# LSM6DS3.net
KiCad netlist of a schematic drawn in Altium Designer
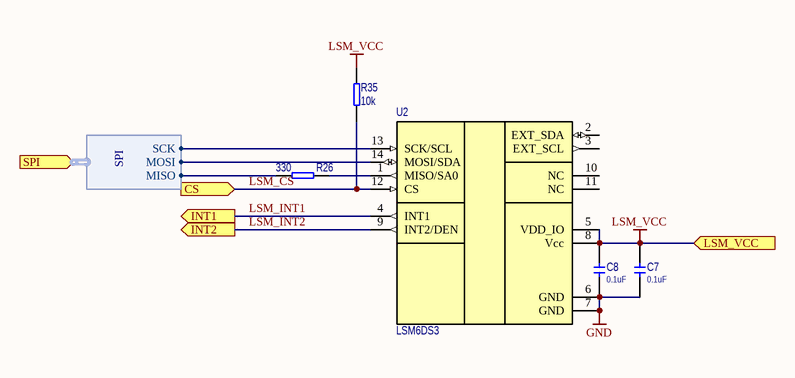
[diagram p0: LSM6DS3.SchDoc]

(export (version "E")
  (design (tool "Eeschema 10.0.6"))
  (components
    (comp (ref "C7")
      (value "0.1uF")
      (footprint "CERCAP 0603")
      (description "Capacitor")
      (fields (field (name "Comment") "CERCAP 0603 0.1uF * X7R"))
      (libsource (lib "!main") (part "!Capacitor"))
    )
    (comp (ref "C8")
      (value "0.1uF")
      (footprint "CERCAP 0603")
      (description "Capacitor")
      (fields (field (name "Comment") "CERCAP 0603 0.1uF * X7R"))
      (libsource (lib "!main") (part "!Capacitor"))
    )
    (comp (ref "R26")
      (value "330")
      (footprint "RES 0603")
      (description "Resistor")
      (fields (field (name "Comment") "RES 0603 330"))
      (libsource (lib "!main") (part "!Resistor"))
    )
    (comp (ref "R35")
      (value "10k")
      (footprint "RES 0603")
      (description "Resistor")
      (fields (field (name "Comment") "RES 0603 10k"))
      (libsource (lib "!main") (part "!Resistor"))
    )
    (comp (ref "U2")
      (value "LSM6DS3")
      (footprint "LGA14_LSM6DS3")
      (description "Acc/Gyro")
      (libsource (lib "sensors") (part "LSM6DS3"))
    )
  )
  (nets
    (net (code "2") (name "/LSM_CS") (class "Default")
      (node (ref "R35") (pin "1") (pinfunction "11_1") (pintype "passive"))
      (node (ref "U2") (pin "12") (pinfunction "CS_12") (pintype "input"))
    )
    (net (code "3") (name "/LSM_INT1") (class "Default")
      (node (ref "U2") (pin "4") (pinfunction "INT1_4") (pintype "output"))
    )
    (net (code "4") (name "/LSM_INT2") (class "Default")
      (node (ref "U2") (pin "9") (pinfunction "INT2/DEN_9") (pintype "output"))
    )
    (net (code "5") (name "/MISO") (class "Default")
      (node (ref "R26") (pin "1") (pinfunction "11_1") (pintype "passive"))
    )
    (net (code "6") (name "/MOSI") (class "Default")
      (node (ref "U2") (pin "14") (pinfunction "MOSI/SDA_14") (pintype "bidirectional"))
    )
    (net (code "7") (name "/SCK") (class "Default")
      (node (ref "U2") (pin "13") (pinfunction "SCK/SCL_13") (pintype "input"))
    )
    (net (code "9") (name "GND") (class "Default")
      (node (ref "C7") (pin "1") (pintype "passive"))
      (node (ref "C8") (pin "1") (pintype "passive"))
      (node (ref "U2") (pin "6") (pinfunction "GND_6") (pintype "power_in"))
      (node (ref "U2") (pin "7") (pinfunction "GND_7") (pintype "power_in"))
    )
    (net (code "10") (name "LSM_VCC") (class "Default")
      (node (ref "C7") (pin "2") (pintype "passive"))
      (node (ref "C8") (pin "2") (pintype "passive"))
      (node (ref "R35") (pin "2") (pinfunction "12_2") (pintype "passive"))
      (node (ref "U2") (pin "5") (pinfunction "VDD_IO_5") (pintype "power_in"))
      (node (ref "U2") (pin "8") (pinfunction "Vcc_8") (pintype "power_in"))
    )
    (net (code "11") (name "Net-(R26-12)") (class "Default")
      (node (ref "R26") (pin "2") (pinfunction "12_2") (pintype "passive"))
      (node (ref "U2") (pin "1") (pinfunction "MISO/SA0_1") (pintype "output"))
    )
    (net (code "12") (name "unconnected-(U2-EXT_SCL-Pad3)") (class "Default")
      (node (ref "U2") (pin "3") (pinfunction "EXT_SCL_3") (pintype "output"))
    )
    (net (code "13") (name "unconnected-(U2-EXT_SDA-Pad2)") (class "Default")
      (node (ref "U2") (pin "2") (pinfunction "EXT_SDA_2") (pintype "bidirectional"))
    )
    (net (code "14") (name "unconnected-(U2-NC-Pad10)") (class "Default")
      (node (ref "U2") (pin "10") (pinfunction "NC_10") (pintype "passive"))
    )
    (net (code "15") (name "unconnected-(U2-NC-Pad11)") (class "Default")
      (node (ref "U2") (pin "11") (pinfunction "NC_11") (pintype "passive"))
    )
  )
)
